# ProDoc_OASman_V4_0_2025-09-03.net
KiCad netlist of a schematic drawn in EasyEDA Pro
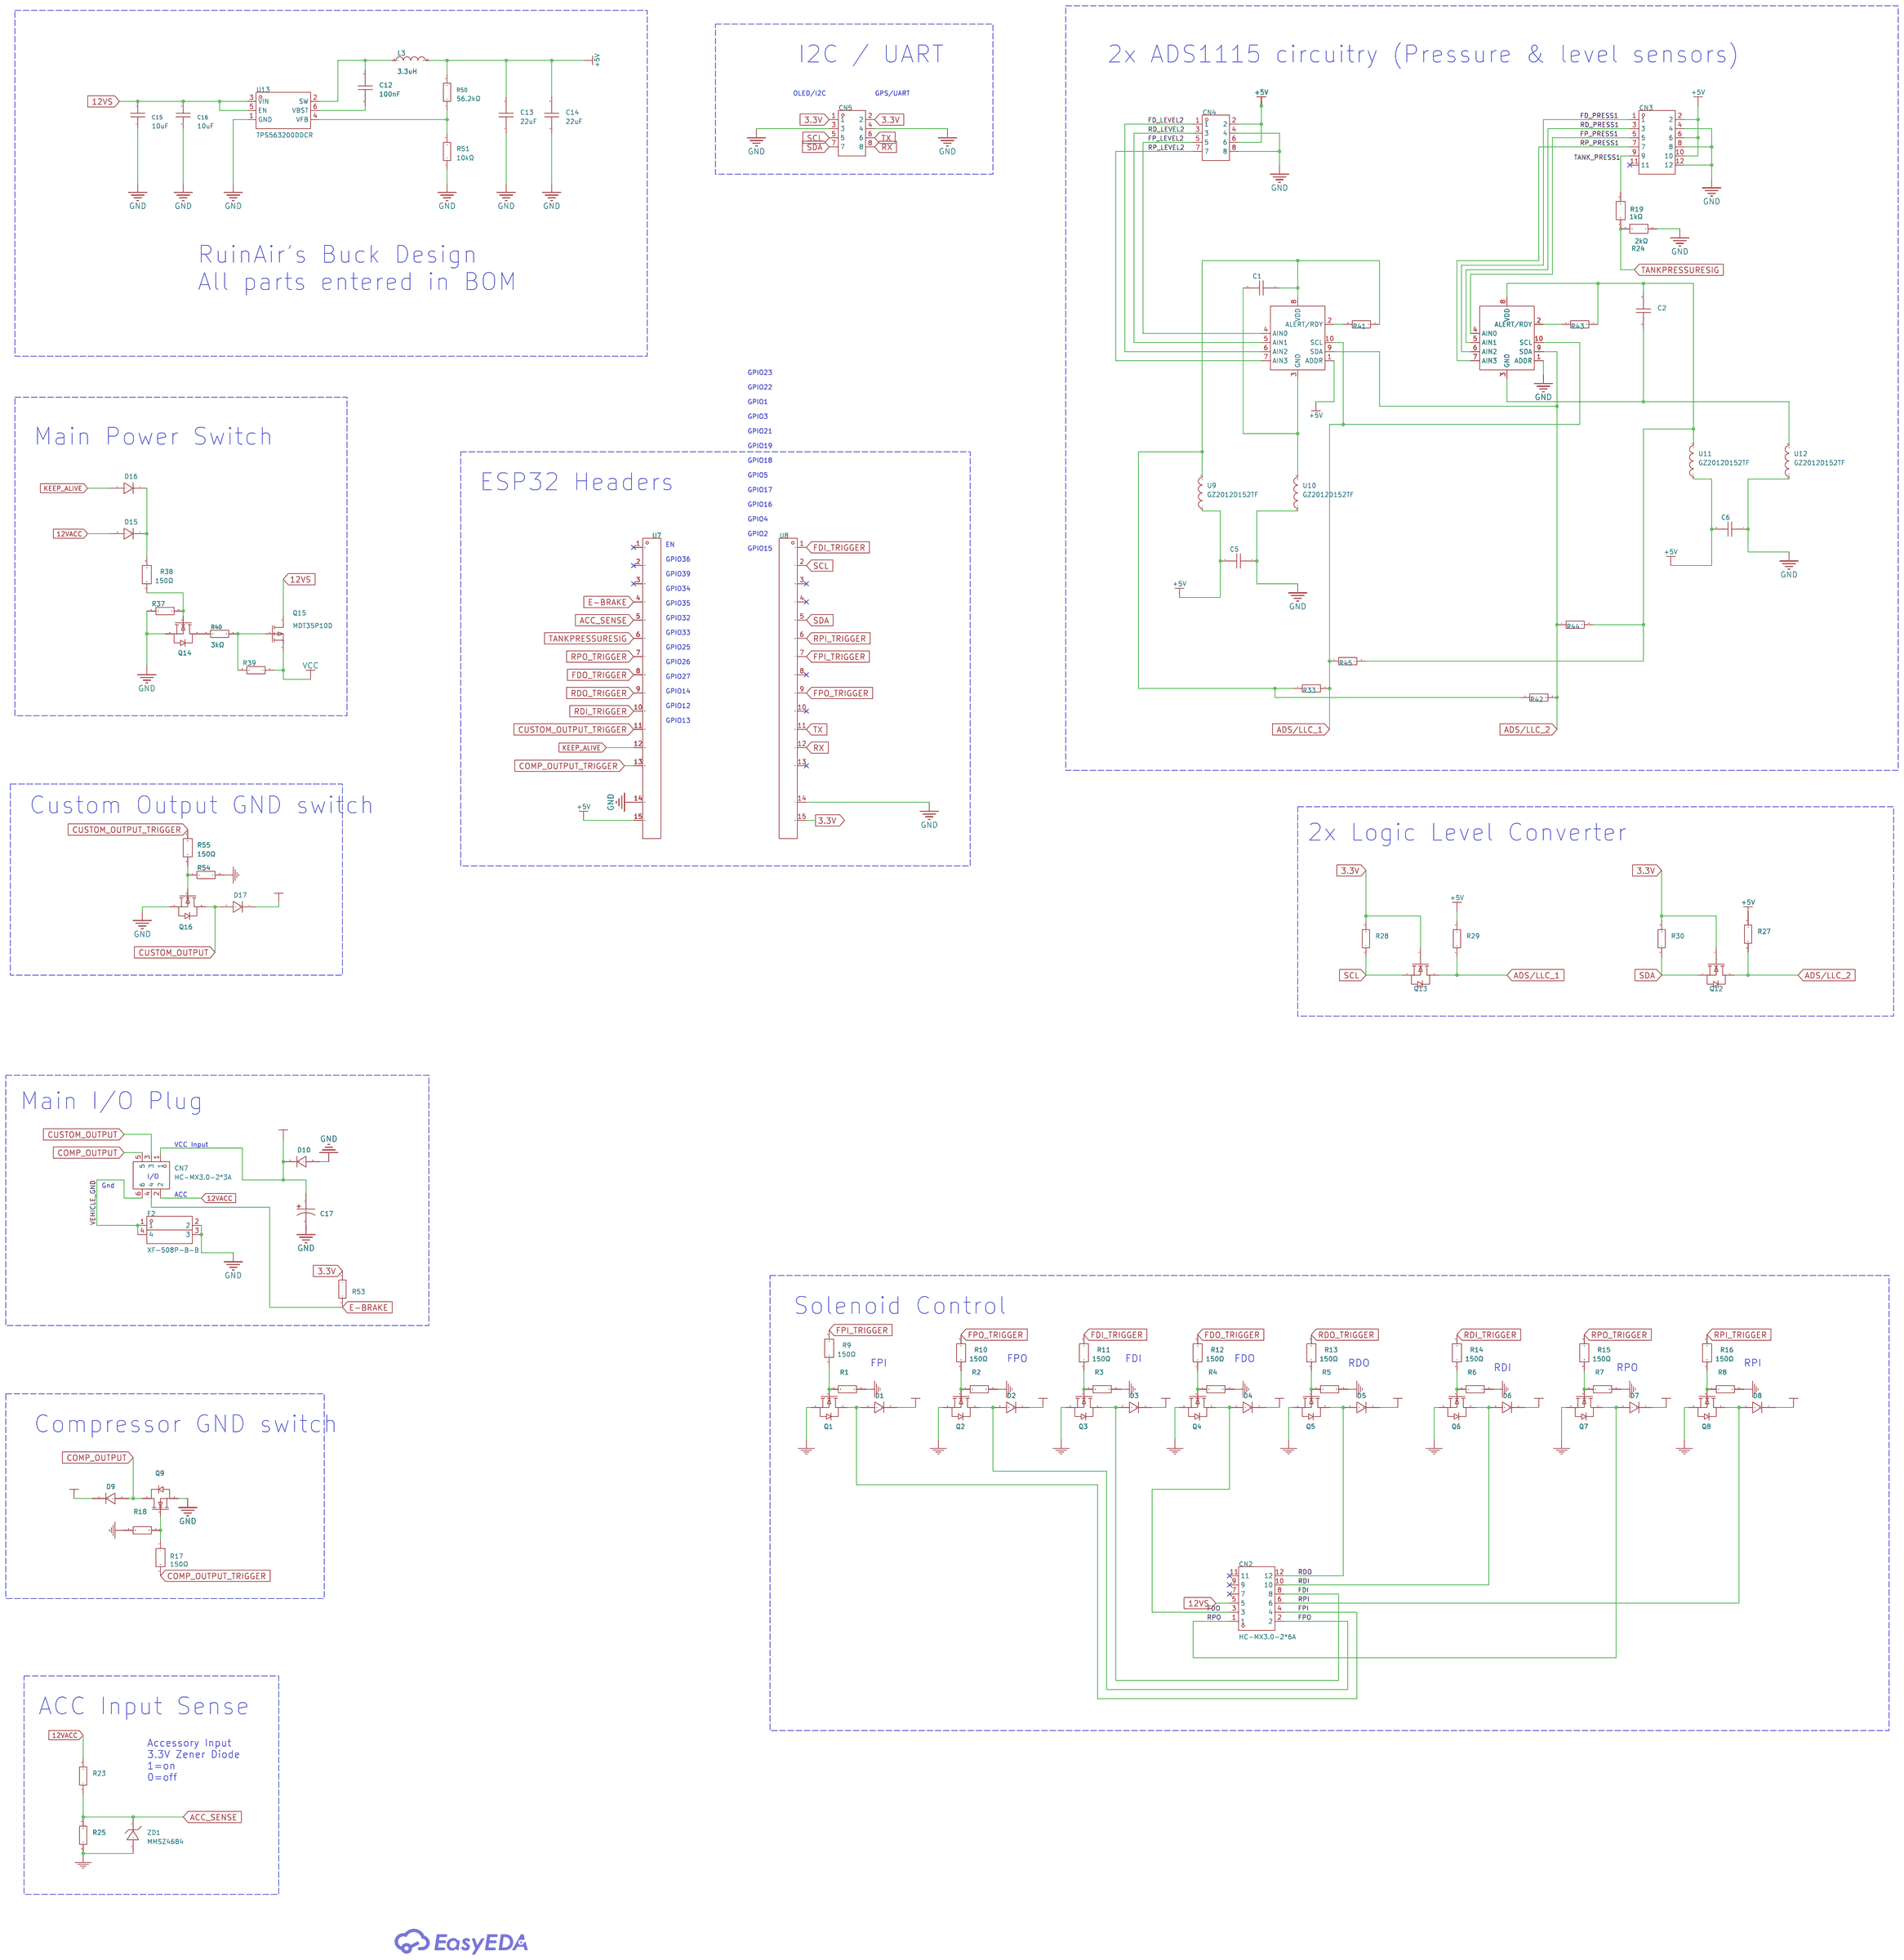
[diagram p0: schematic sheet]

(export (version "E")
  (design (tool "Eeschema 10.0.6"))
  (components
    (comp (ref "C1")
      (value "1uF")
      (footprint "easyedapro:C0603")
      (fields
        (field (name "Manufacturer Part") "GRM188R61H105KAALD")
        (field (name "Manufacturer") "muRata(村田)")
      )
      (libsource (lib "easyedapro") (part "GRM188R61H105KAALD"))
    )
    (comp (ref "C2")
      (value "1uF")
      (footprint "easyedapro:C0603")
      (fields
        (field (name "Manufacturer Part") "GRM188R61H105KAALD")
        (field (name "Manufacturer") "muRata(村田)")
      )
      (libsource (lib "easyedapro") (part "GRM188R61H105KAALD"))
    )
    (comp (ref "C5")
      (value "1uF")
      (footprint "easyedapro:C0603")
      (fields
        (field (name "Manufacturer Part") "GRM188R61H105KAALD")
        (field (name "Manufacturer") "muRata(村田)")
      )
      (libsource (lib "easyedapro") (part "GRM188R61H105KAALD"))
    )
    (comp (ref "C6")
      (value "1uF")
      (footprint "easyedapro:C0603")
      (fields
        (field (name "Manufacturer Part") "GRM188R61H105KAALD")
        (field (name "Manufacturer") "muRata(村田)")
      )
      (libsource (lib "easyedapro") (part "GRM188R61H105KAALD"))
    )
    (comp (ref "C12")
      (value "100nF")
      (footprint "easyedapro:C0402")
      (fields
        (field (name "Manufacturer Part") "CL05B104KB54PNC")
        (field (name "Manufacturer") "SAMSUNG(三星)")
      )
      (libsource (lib "easyedapro") (part "CL05B104KB54PNC"))
    )
    (comp (ref "C13")
      (value "22uF")
      (footprint "easyedapro:C0805")
      (fields
        (field (name "Manufacturer Part") "CL21A226MAQNNNE")
        (field (name "Manufacturer") "SAMSUNG(三星)")
      )
      (libsource (lib "easyedapro") (part "CL21A226MAQNNNE"))
    )
    (comp (ref "C14")
      (value "22uF")
      (footprint "easyedapro:C0805")
      (fields
        (field (name "Manufacturer Part") "CL21A226MAQNNNE")
        (field (name "Manufacturer") "SAMSUNG(三星)")
      )
      (libsource (lib "easyedapro") (part "CL21A226MAQNNNE"))
    )
    (comp (ref "C15")
      (value "10uF")
      (footprint "easyedapro:C1206")
      (fields
        (field (name "Manufacturer Part") "CL31A106KBHNNNE")
        (field (name "Manufacturer") "SAMSUNG(三星)")
      )
      (libsource (lib "easyedapro") (part "CL31A106KBHNNNE"))
    )
    (comp (ref "C16")
      (value "10uF")
      (footprint "easyedapro:C1206")
      (fields
        (field (name "Manufacturer Part") "CL31A106KBHNNNE")
        (field (name "Manufacturer") "SAMSUNG(三星)")
      )
      (libsource (lib "easyedapro") (part "CL31A106KBHNNNE"))
    )
    (comp (ref "C17")
      (value "1000uF")
      (footprint "easyedapro:CAP-SMD_BD10.0-L10.3-W10.3-FD")
      (fields (field (name "Manufacturer Part") "EEEFT1E102UP") (field (name "Manufacturer") "PANASONIC(松下)"))
      (libsource (lib "easyedapro") (part "EEEFT1E102UP"))
    )
    (comp (ref "CN2")
      (value "HC-MX3.0-2*6A")
      (footprint "easyedapro:CONN-TH_12P-P3.00_HC-MX3.0-2X6A")
      (fields (field (name "Manufacturer") "HCTL(华灿天禄)"))
      (libsource (lib "easyedapro") (part "HC-MX3.0-2*6A"))
    )
    (comp (ref "CN3")
      (value "HC-MX3.0-2*6A")
      (footprint "easyedapro:CONN-TH_12P-P3.00_HC-MX3.0-2X6A")
      (fields (field (name "Manufacturer") "HCTL(华灿天禄)"))
      (libsource (lib "easyedapro") (part "HC-MX3.0-2*6A"))
    )
    (comp (ref "CN4")
      (value "HC-MX3.0-2*4A")
      (footprint "easyedapro:CONN-TH_8P-P3.00_HC-MX3.0-2X4A")
      (fields (field (name "Manufacturer") "HCTL(华灿天禄)"))
      (libsource (lib "easyedapro") (part "HC-MX3.0-2*4A"))
    )
    (comp (ref "CN5")
      (value "HC-MX3.0-2*4A")
      (footprint "easyedapro:CONN-TH_8P-P3.00_HC-MX3.0-2X4A")
      (fields (field (name "Manufacturer") "HCTL(华灿天禄)"))
      (libsource (lib "easyedapro") (part "HC-MX3.0-2*4A"))
    )
    (comp (ref "CN7")
      (value "HC-MX3.0-2*3A")
      (footprint "easyedapro:CONN-TH_6P-P3.00_HC-MX3.0-2X3A")
      (fields (field (name "Manufacturer") "HCTL(华灿天禄)"))
      (libsource (lib "easyedapro") (part "HC-MX3.0-2*3A"))
    )
    (comp (ref "D1")
      (value "SM4007PL")
      (footprint "easyedapro:SOD-123F_L2.8-W1.8-LS3.7-RD")
      (fields (field (name "Manufacturer") "MDD(辰达半导体)"))
      (libsource (lib "easyedapro") (part "SM4007PL"))
    )
    (comp (ref "D2")
      (value "SM4007PL")
      (footprint "easyedapro:SOD-123F_L2.8-W1.8-LS3.7-RD")
      (fields (field (name "Manufacturer") "MDD(辰达半导体)"))
      (libsource (lib "easyedapro") (part "SM4007PL"))
    )
    (comp (ref "D3")
      (value "SM4007PL")
      (footprint "easyedapro:SOD-123F_L2.8-W1.8-LS3.7-RD")
      (fields (field (name "Manufacturer") "MDD(辰达半导体)"))
      (libsource (lib "easyedapro") (part "SM4007PL"))
    )
    (comp (ref "D4")
      (value "SM4007PL")
      (footprint "easyedapro:SOD-123F_L2.8-W1.8-LS3.7-RD")
      (fields (field (name "Manufacturer") "MDD(辰达半导体)"))
      (libsource (lib "easyedapro") (part "SM4007PL"))
    )
    (comp (ref "D5")
      (value "SM4007PL")
      (footprint "easyedapro:SOD-123F_L2.8-W1.8-LS3.7-RD")
      (fields (field (name "Manufacturer") "MDD(辰达半导体)"))
      (libsource (lib "easyedapro") (part "SM4007PL"))
    )
    (comp (ref "D6")
      (value "SM4007PL")
      (footprint "easyedapro:SOD-123F_L2.8-W1.8-LS3.7-RD")
      (fields (field (name "Manufacturer") "MDD(辰达半导体)"))
      (libsource (lib "easyedapro") (part "SM4007PL"))
    )
    (comp (ref "D7")
      (value "SM4007PL")
      (footprint "easyedapro:SOD-123F_L2.8-W1.8-LS3.7-RD")
      (fields (field (name "Manufacturer") "MDD(辰达半导体)"))
      (libsource (lib "easyedapro") (part "SM4007PL"))
    )
    (comp (ref "D8")
      (value "SM4007PL")
      (footprint "easyedapro:SOD-123F_L2.8-W1.8-LS3.7-RD")
      (fields (field (name "Manufacturer") "MDD(辰达半导体)"))
      (libsource (lib "easyedapro") (part "SM4007PL"))
    )
    (comp (ref "D9")
      (value "SM4007PL")
      (footprint "easyedapro:SOD-123F_L2.8-W1.8-LS3.7-RD")
      (fields (field (name "Manufacturer") "MDD(辰达半导体)"))
      (libsource (lib "easyedapro") (part "SM4007PL"))
    )
    (comp (ref "D10")
      (value "SM4007PL")
      (footprint "easyedapro:SOD-123F_L2.8-W1.8-LS3.7-RD")
      (fields (field (name "Manufacturer") "MDD(辰达半导体)"))
      (libsource (lib "easyedapro") (part "SM4007PL"))
    )
    (comp (ref "D15")
      (value "SM4007PL")
      (footprint "easyedapro:SOD-123F_L2.8-W1.8-LS3.7-RD")
      (fields (field (name "Manufacturer") "MDD(辰达半导体)"))
      (libsource (lib "easyedapro") (part "SM4007PL"))
    )
    (comp (ref "D16")
      (value "SM4007PL")
      (footprint "easyedapro:SOD-123F_L2.8-W1.8-LS3.7-RD")
      (fields (field (name "Manufacturer") "MDD(辰达半导体)"))
      (libsource (lib "easyedapro") (part "SM4007PL"))
    )
    (comp (ref "D17")
      (value "SM4007PL")
      (footprint "easyedapro:SOD-123F_L2.8-W1.8-LS3.7-RD")
      (fields (field (name "Manufacturer") "MDD(辰达半导体)"))
      (libsource (lib "easyedapro") (part "SM4007PL"))
    )
    (comp (ref "F2")
      (value "XF-508P-B-B")
      (footprint "easyedapro:FUSE-TH_4P-L16.0-W6.7")
      (fields (field (name "Manufacturer") "XFCN(兴飞)"))
      (libsource (lib "easyedapro") (part "XF-508P-B-B"))
    )
    (comp (ref "L3")
      (value "3.3uH")
      (footprint "easyedapro:IND-SMD_L4.5-W4.1_SL0420")
      (description "Inductance: Tolerance:±20% Tolerance:±20% Rated Current: Saturation Current (Isat):4A")
      (fields (field (name "Manufacturer Part") "SL0420-3R3M") (field (name "Manufacturer") "台湾陆海"))
      (libsource (lib "easyedapro") (part "SL0420-3R3M"))
    )
    (comp (ref "Q1") (value "MDT30N06L") (libsource (lib "easyedapro") (part "FQP30N06L")))
    (comp (ref "Q2") (value "MDT30N06L") (libsource (lib "easyedapro") (part "FQP30N06L")))
    (comp (ref "Q3") (value "MDT30N06L") (libsource (lib "easyedapro") (part "FQP30N06L")))
    (comp (ref "Q4") (value "MDT30N06L") (libsource (lib "easyedapro") (part "FQP30N06L")))
    (comp (ref "Q5") (value "MDT30N06L") (libsource (lib "easyedapro") (part "FQP30N06L")))
    (comp (ref "Q6") (value "MDT30N06L") (libsource (lib "easyedapro") (part "FQP30N06L")))
    (comp (ref "Q7") (value "MDT30N06L") (libsource (lib "easyedapro") (part "FQP30N06L")))
    (comp (ref "Q8") (value "MDT30N06L") (libsource (lib "easyedapro") (part "FQP30N06L")))
    (comp (ref "Q9") (value "MDT30N06L") (libsource (lib "easyedapro") (part "FQP30N06L")))
    (comp (ref "Q12")
      (value "BSS138")
      (footprint "easyedapro:SOT-23-3_L2.9-W1.6-P1.90-LS2.8-BR")
      (fields (field (name "Manufacturer") "SHIKUES(时科)"))
      (libsource (lib "easyedapro") (part "BSS138_C112239"))
    )
    (comp (ref "Q13")
      (value "BSS138")
      (footprint "easyedapro:SOT-23-3_L2.9-W1.6-P1.90-LS2.8-BR")
      (fields (field (name "Manufacturer") "SHIKUES(时科)"))
      (libsource (lib "easyedapro") (part "BSS138_C112239"))
    )
    (comp (ref "Q14") (value "MDT30N06L") (libsource (lib "easyedapro") (part "FQP30N06L")))
    (comp (ref "Q15")
      (value "MDT35P10D")
      (footprint "easyedapro:TO-252-2_L6.6-W6.1-P4.57-LS9.9-BR-CW")
      (fields (field (name "Manufacturer") "minos(迈诺斯)"))
      (libsource (lib "easyedapro") (part "MDT35P10D"))
    )
    (comp (ref "Q16") (value "MDT30N06L") (libsource (lib "easyedapro") (part "FQP30N06L")))
    (comp (ref "R1")
      (value "10kΩ")
      (footprint "easyedapro:R1206")
      (fields
        (field (name "Manufacturer Part") "1206W4F1002T5E")
        (field (name "Manufacturer") "UNI-ROYAL(厚声)")
      )
      (libsource (lib "easyedapro") (part "1206W4F1002T5E"))
    )
    (comp (ref "R2")
      (value "10kΩ")
      (footprint "easyedapro:R1206")
      (fields
        (field (name "Manufacturer Part") "1206W4F1002T5E")
        (field (name "Manufacturer") "UNI-ROYAL(厚声)")
      )
      (libsource (lib "easyedapro") (part "1206W4F1002T5E"))
    )
    (comp (ref "R3")
      (value "10kΩ")
      (footprint "easyedapro:R1206")
      (fields
        (field (name "Manufacturer Part") "1206W4F1002T5E")
        (field (name "Manufacturer") "UNI-ROYAL(厚声)")
      )
      (libsource (lib "easyedapro") (part "1206W4F1002T5E"))
    )
    (comp (ref "R4")
      (value "10kΩ")
      (footprint "easyedapro:R1206")
      (fields
        (field (name "Manufacturer Part") "1206W4F1002T5E")
        (field (name "Manufacturer") "UNI-ROYAL(厚声)")
      )
      (libsource (lib "easyedapro") (part "1206W4F1002T5E"))
    )
    (comp (ref "R5")
      (value "10kΩ")
      (footprint "easyedapro:R1206")
      (fields
        (field (name "Manufacturer Part") "1206W4F1002T5E")
        (field (name "Manufacturer") "UNI-ROYAL(厚声)")
      )
      (libsource (lib "easyedapro") (part "1206W4F1002T5E"))
    )
    (comp (ref "R6")
      (value "10kΩ")
      (footprint "easyedapro:R1206")
      (fields
        (field (name "Manufacturer Part") "1206W4F1002T5E")
        (field (name "Manufacturer") "UNI-ROYAL(厚声)")
      )
      (libsource (lib "easyedapro") (part "1206W4F1002T5E"))
    )
    (comp (ref "R7")
      (value "10kΩ")
      (footprint "easyedapro:R1206")
      (fields
        (field (name "Manufacturer Part") "1206W4F1002T5E")
        (field (name "Manufacturer") "UNI-ROYAL(厚声)")
      )
      (libsource (lib "easyedapro") (part "1206W4F1002T5E"))
    )
    (comp (ref "R8")
      (value "10kΩ")
      (footprint "easyedapro:R1206")
      (fields
        (field (name "Manufacturer Part") "1206W4F1002T5E")
        (field (name "Manufacturer") "UNI-ROYAL(厚声)")
      )
      (libsource (lib "easyedapro") (part "1206W4F1002T5E"))
    )
    (comp (ref "R9")
      (value "150Ω")
      (footprint "easyedapro:R1206")
      (fields (field (name "Manufacturer Part") "FRC1206J151 TS") (field (name "Manufacturer") "FOJAN(富捷)"))
      (libsource (lib "easyedapro") (part "FRC1206J151 TS"))
    )
    (comp (ref "R10")
      (value "150Ω")
      (footprint "easyedapro:R1206")
      (fields (field (name "Manufacturer Part") "FRC1206J151 TS") (field (name "Manufacturer") "FOJAN(富捷)"))
      (libsource (lib "easyedapro") (part "FRC1206J151 TS"))
    )
    (comp (ref "R11")
      (value "150Ω")
      (footprint "easyedapro:R1206")
      (fields (field (name "Manufacturer Part") "FRC1206J151 TS") (field (name "Manufacturer") "FOJAN(富捷)"))
      (libsource (lib "easyedapro") (part "FRC1206J151 TS"))
    )
    (comp (ref "R12")
      (value "150Ω")
      (footprint "easyedapro:R1206")
      (fields (field (name "Manufacturer Part") "FRC1206J151 TS") (field (name "Manufacturer") "FOJAN(富捷)"))
      (libsource (lib "easyedapro") (part "FRC1206J151 TS"))
    )
    (comp (ref "R13")
      (value "150Ω")
      (footprint "easyedapro:R1206")
      (fields (field (name "Manufacturer Part") "FRC1206J151 TS") (field (name "Manufacturer") "FOJAN(富捷)"))
      (libsource (lib "easyedapro") (part "FRC1206J151 TS"))
    )
    (comp (ref "R14")
      (value "150Ω")
      (footprint "easyedapro:R1206")
      (fields (field (name "Manufacturer Part") "FRC1206J151 TS") (field (name "Manufacturer") "FOJAN(富捷)"))
      (libsource (lib "easyedapro") (part "FRC1206J151 TS"))
    )
    (comp (ref "R15")
      (value "150Ω")
      (footprint "easyedapro:R1206")
      (fields (field (name "Manufacturer Part") "FRC1206J151 TS") (field (name "Manufacturer") "FOJAN(富捷)"))
      (libsource (lib "easyedapro") (part "FRC1206J151 TS"))
    )
    (comp (ref "R16")
      (value "150Ω")
      (footprint "easyedapro:R1206")
      (fields (field (name "Manufacturer Part") "FRC1206J151 TS") (field (name "Manufacturer") "FOJAN(富捷)"))
      (libsource (lib "easyedapro") (part "FRC1206J151 TS"))
    )
    (comp (ref "R17")
      (value "150Ω")
      (footprint "easyedapro:R1206")
      (fields (field (name "Manufacturer Part") "FRC1206J151 TS") (field (name "Manufacturer") "FOJAN(富捷)"))
      (libsource (lib "easyedapro") (part "FRC1206J151 TS"))
    )
    (comp (ref "R18")
      (value "10kΩ")
      (footprint "easyedapro:R1206")
      (fields
        (field (name "Manufacturer Part") "1206W4F1002T5E")
        (field (name "Manufacturer") "UNI-ROYAL(厚声)")
      )
      (libsource (lib "easyedapro") (part "1206W4F1002T5E"))
    )
    (comp (ref "R19")
      (value "1kΩ")
      (footprint "easyedapro:R1206")
      (fields (field (name "Manufacturer Part") "FRC1206J102 TS") (field (name "Manufacturer") "FOJAN(富捷)"))
      (libsource (lib "easyedapro") (part "FRC1206J102 TS"))
    )
    (comp (ref "R23")
      (value "10kΩ")
      (footprint "easyedapro:R1206")
      (fields
        (field (name "Manufacturer Part") "1206W4F1002T5E")
        (field (name "Manufacturer") "UNI-ROYAL(厚声)")
      )
      (libsource (lib "easyedapro") (part "1206W4F1002T5E"))
    )
    (comp (ref "R24")
      (value "2kΩ")
      (footprint "easyedapro:R1206")
      (fields (field (name "Manufacturer Part") "FRC1206J202 TS") (field (name "Manufacturer") "FOJAN(富捷)"))
      (libsource (lib "easyedapro") (part "FRC1206J202 TS"))
    )
    (comp (ref "R25")
      (value "10kΩ")
      (footprint "easyedapro:R1206")
      (fields
        (field (name "Manufacturer Part") "1206W4F1002T5E")
        (field (name "Manufacturer") "UNI-ROYAL(厚声)")
      )
      (libsource (lib "easyedapro") (part "1206W4F1002T5E"))
    )
    (comp (ref "R27")
      (value "10kΩ")
      (footprint "easyedapro:R1206")
      (fields
        (field (name "Manufacturer Part") "1206W4F1002T5E")
        (field (name "Manufacturer") "UNI-ROYAL(厚声)")
      )
      (libsource (lib "easyedapro") (part "1206W4F1002T5E"))
    )
    (comp (ref "R28")
      (value "10kΩ")
      (footprint "easyedapro:R1206")
      (fields
        (field (name "Manufacturer Part") "1206W4F1002T5E")
        (field (name "Manufacturer") "UNI-ROYAL(厚声)")
      )
      (libsource (lib "easyedapro") (part "1206W4F1002T5E"))
    )
    (comp (ref "R29")
      (value "10kΩ")
      (footprint "easyedapro:R1206")
      (fields
        (field (name "Manufacturer Part") "1206W4F1002T5E")
        (field (name "Manufacturer") "UNI-ROYAL(厚声)")
      )
      (libsource (lib "easyedapro") (part "1206W4F1002T5E"))
    )
    (comp (ref "R30")
      (value "10kΩ")
      (footprint "easyedapro:R1206")
      (fields
        (field (name "Manufacturer Part") "1206W4F1002T5E")
        (field (name "Manufacturer") "UNI-ROYAL(厚声)")
      )
      (libsource (lib "easyedapro") (part "1206W4F1002T5E"))
    )
    (comp (ref "R33")
      (value "1MΩ")
      (footprint "easyedapro:R1206")
      (fields
        (field (name "Manufacturer Part") "1206W4F1004T5E")
        (field (name "Manufacturer") "UNI-ROYAL(厚声)")
      )
      (libsource (lib "easyedapro") (part "1206W4F1004T5E"))
    )
    (comp (ref "R37")
      (value "10kΩ")
      (footprint "easyedapro:R1206")
      (fields
        (field (name "Manufacturer Part") "1206W4F1002T5E")
        (field (name "Manufacturer") "UNI-ROYAL(厚声)")
      )
      (libsource (lib "easyedapro") (part "1206W4F1002T5E"))
    )
    (comp (ref "R38")
      (value "150Ω")
      (footprint "easyedapro:R1206")
      (fields (field (name "Manufacturer Part") "FRC1206J151 TS") (field (name "Manufacturer") "FOJAN(富捷)"))
      (libsource (lib "easyedapro") (part "FRC1206J151 TS"))
    )
    (comp (ref "R39")
      (value "10kΩ")
      (footprint "easyedapro:R1206")
      (fields
        (field (name "Manufacturer Part") "1206W4F1002T5E")
        (field (name "Manufacturer") "UNI-ROYAL(厚声)")
      )
      (libsource (lib "easyedapro") (part "1206W4F1002T5E"))
    )
    (comp (ref "R40")
      (value "3kΩ")
      (footprint "easyedapro:R1206")
      (fields
        (field (name "Manufacturer Part") "1206W4F3001T5E")
        (field (name "Manufacturer") "UNI-ROYAL(厚声)")
      )
      (libsource (lib "easyedapro") (part "1206W4F3001T5E"))
    )
    (comp (ref "R41")
      (value "1MΩ")
      (footprint "easyedapro:R1206")
      (fields
        (field (name "Manufacturer Part") "1206W4F1004T5E")
        (field (name "Manufacturer") "UNI-ROYAL(厚声)")
      )
      (libsource (lib "easyedapro") (part "1206W4F1004T5E"))
    )
    (comp (ref "R42")
      (value "1MΩ")
      (footprint "easyedapro:R1206")
      (fields
        (field (name "Manufacturer Part") "1206W4F1004T5E")
        (field (name "Manufacturer") "UNI-ROYAL(厚声)")
      )
      (libsource (lib "easyedapro") (part "1206W4F1004T5E"))
    )
    (comp (ref "R43")
      (value "1MΩ")
      (footprint "easyedapro:R1206")
      (fields
        (field (name "Manufacturer Part") "1206W4F1004T5E")
        (field (name "Manufacturer") "UNI-ROYAL(厚声)")
      )
      (libsource (lib "easyedapro") (part "1206W4F1004T5E"))
    )
    (comp (ref "R44")
      (value "1MΩ")
      (footprint "easyedapro:R1206")
      (fields
        (field (name "Manufacturer Part") "1206W4F1004T5E")
        (field (name "Manufacturer") "UNI-ROYAL(厚声)")
      )
      (libsource (lib "easyedapro") (part "1206W4F1004T5E"))
    )
    (comp (ref "R45")
      (value "1MΩ")
      (footprint "easyedapro:R1206")
      (fields
        (field (name "Manufacturer Part") "1206W4F1004T5E")
        (field (name "Manufacturer") "UNI-ROYAL(厚声)")
      )
      (libsource (lib "easyedapro") (part "1206W4F1004T5E"))
    )
    (comp (ref "R50")
      (value "56.2kΩ")
      (footprint "easyedapro:R0402")
      (fields
        (field (name "Manufacturer Part") "0402WGF5622TCE")
        (field (name "Manufacturer") "UNI-ROYAL(厚声)")
      )
      (libsource (lib "easyedapro") (part "0402WGF5622TCE"))
    )
    (comp (ref "R51")
      (value "10kΩ")
      (footprint "easyedapro:R0402")
      (fields
        (field (name "Manufacturer Part") "0402WGF1002TCE")
        (field (name "Manufacturer") "UNI-ROYAL(厚声)")
      )
      (libsource (lib "easyedapro") (part "0402WGF1002TCE"))
    )
    (comp (ref "R53")
      (value "10kΩ")
      (footprint "easyedapro:R1206")
      (fields
        (field (name "Manufacturer Part") "1206W4F1002T5E")
        (field (name "Manufacturer") "UNI-ROYAL(厚声)")
      )
      (libsource (lib "easyedapro") (part "1206W4F1002T5E"))
    )
    (comp (ref "R54")
      (value "10kΩ")
      (footprint "easyedapro:R1206")
      (fields
        (field (name "Manufacturer Part") "1206W4F1002T5E")
        (field (name "Manufacturer") "UNI-ROYAL(厚声)")
      )
      (libsource (lib "easyedapro") (part "1206W4F1002T5E"))
    )
    (comp (ref "R55")
      (value "150Ω")
      (footprint "easyedapro:R1206")
      (fields (field (name "Manufacturer Part") "FRC1206J151 TS") (field (name "Manufacturer") "FOJAN(富捷)"))
      (libsource (lib "easyedapro") (part "FRC1206J151 TS"))
    )
    (comp (ref "U4")
      (value "ADS1115IDGSR")
      (fields (field (name "Manufacturer") "TI(德州仪器)"))
      (libsource (lib "easyedapro") (part "Analog_ADC_ADS1115IDGS"))
    )
    (comp (ref "U5")
      (value "ADS1115IDGSR")
      (fields (field (name "Manufacturer") "TI(德州仪器)"))
      (libsource (lib "easyedapro") (part "Analog_ADC_ADS1115IDGS"))
    )
    (comp (ref "U7")
      (value "PM2.54-1*15")
      (footprint "easyedapro:HDR-TH_15P-P2.54-V-F")
      (description "Holes Structure:1x15P Pitch:2.54mm Number of Rows:Plugin Contact Plating:Gold")
      (fields (field (name "Manufacturer") "ZHOURI(洲日)"))
      (libsource (lib "easyedapro") (part "FH2.54-09-15PZD"))
    )
    (comp (ref "U8")
      (value "PM2.54-1*15")
      (footprint "easyedapro:HDR-TH_15P-P2.54-V-F")
      (description "Holes Structure:1x15P Pitch:2.54mm Number of Rows:Plugin Contact Plating:Gold")
      (fields (field (name "Manufacturer") "ZHOURI(洲日)"))
      (libsource (lib "easyedapro") (part "FH2.54-09-15PZD"))
    )
    (comp (ref "U9")
      (value "GZ2012D152TF")
      (fields (field (name "Manufacturer") "Sunlord(顺络)"))
      (libsource (lib "easyedapro") (part "MMZ2012Y152BT000"))
    )
    (comp (ref "U10")
      (value "GZ2012D152TF")
      (fields (field (name "Manufacturer") "Sunlord(顺络)"))
      (libsource (lib "easyedapro") (part "MMZ2012Y152BT000"))
    )
    (comp (ref "U11")
      (value "GZ2012D152TF")
      (fields (field (name "Manufacturer") "Sunlord(顺络)"))
      (libsource (lib "easyedapro") (part "MMZ2012Y152BT000"))
    )
    (comp (ref "U12")
      (value "GZ2012D152TF")
      (fields (field (name "Manufacturer") "Sunlord(顺络)"))
      (libsource (lib "easyedapro") (part "MMZ2012Y152BT000"))
    )
    (comp (ref "U13")
      (value "TPS563200DDCR")
      (footprint "easyedapro:SOT-23-6_L2.9-W1.6-P0.95-LS2.8-BR")
      (fields (field (name "Manufacturer") "TI(德州仪器)"))
      (libsource (lib "easyedapro") (part "TPS563200DDCR"))
    )
    (comp (ref "ZD1")
      (value "MMSZ4684")
      (footprint "easyedapro:SOD-123_L2.8-W1.8-LS3.7-RD")
      (fields (field (name "Manufacturer") "CJ(江苏长电/长晶)"))
      (libsource (lib "easyedapro") (part "MMSZ4684"))
    )
  )
  (nets
    (net (code "1") (name "+5V") (class "Default")
      (node (ref "C13") (pin "2") (pinfunction "2_2") (pintype "unspecified"))
      (node (ref "C14") (pin "2") (pinfunction "2_2") (pintype "unspecified"))
      (node (ref "C5") (pin "2") (pinfunction "2_2") (pintype "unspecified"))
      (node (ref "C6") (pin "2") (pinfunction "2_2") (pintype "unspecified"))
      (node (ref "CN3") (pin "10") (pinfunction "10_10") (pintype "unspecified"))
      (node (ref "CN3") (pin "2") (pinfunction "2_2") (pintype "unspecified"))
      (node (ref "CN3") (pin "6") (pinfunction "6_6") (pintype "unspecified"))
      (node (ref "CN4") (pin "2") (pinfunction "2_2") (pintype "unspecified"))
      (node (ref "CN4") (pin "6") (pinfunction "6_6") (pintype "unspecified"))
      (node (ref "L3") (pin "2") (pinfunction "2_2") (pintype "unspecified"))
      (node (ref "R27") (pin "1") (pinfunction "1_1") (pintype "input"))
      (node (ref "R29") (pin "2") (pinfunction "2_2") (pintype "input"))
      (node (ref "R50") (pin "2") (pinfunction "2_2") (pintype "input"))
      (node (ref "U11") (pin "1") (pinfunction "1_1") (pintype "input"))
      (node (ref "U4") (pin "1") (pinfunction "ADDR_1") (pintype "input"))
      (node (ref "U7") (pin "15") (pinfunction "15_15") (pintype "unspecified"))
      (node (ref "U9") (pin "1") (pinfunction "1_1") (pintype "input"))
    )
    (net (code "2") (name "/FDI") (class "Default")
      (node (ref "CN2") (pin "8") (pinfunction "8_8") (pintype "unspecified"))
      (node (ref "D3") (pin "2") (pinfunction "A_2") (pintype "unspecified"))
      (node (ref "Q3") (pin "2") (pinfunction "D_2") (pintype "unspecified"))
    )
    (net (code "3") (name "/FDO") (class "Default")
      (node (ref "CN2") (pin "3") (pinfunction "3_3") (pintype "unspecified"))
      (node (ref "D4") (pin "2") (pinfunction "A_2") (pintype "unspecified"))
      (node (ref "Q4") (pin "2") (pinfunction "D_2") (pintype "unspecified"))
    )
    (net (code "4") (name "/FD_LEVEL2") (class "Default")
      (node (ref "CN4") (pin "1") (pinfunction "1_1") (pintype "unspecified"))
      (node (ref "U4") (pin "6") (pinfunction "AIN2_6") (pintype "input"))
    )
    (net (code "5") (name "/FD_PRESS1") (class "Default")
      (node (ref "CN3") (pin "1") (pinfunction "1_1") (pintype "unspecified"))
      (node (ref "U5") (pin "6") (pinfunction "AIN2_6") (pintype "input"))
    )
    (net (code "6") (name "/FPI") (class "Default")
      (node (ref "CN2") (pin "4") (pinfunction "4_4") (pintype "unspecified"))
      (node (ref "D1") (pin "2") (pinfunction "A_2") (pintype "unspecified"))
      (node (ref "Q1") (pin "2") (pinfunction "D_2") (pintype "unspecified"))
    )
    (net (code "7") (name "/FPO") (class "Default")
      (node (ref "CN2") (pin "2") (pinfunction "2_2") (pintype "unspecified"))
      (node (ref "D2") (pin "2") (pinfunction "A_2") (pintype "unspecified"))
      (node (ref "Q2") (pin "2") (pinfunction "D_2") (pintype "unspecified"))
    )
    (net (code "8") (name "/FP_LEVEL2") (class "Default")
      (node (ref "CN4") (pin "5") (pinfunction "5_5") (pintype "unspecified"))
      (node (ref "U4") (pin "4") (pinfunction "AIN0_4") (pintype "input"))
    )
    (net (code "9") (name "/FP_PRESS1") (class "Default")
      (node (ref "CN3") (pin "5") (pinfunction "5_5") (pintype "unspecified"))
      (node (ref "U5") (pin "4") (pinfunction "AIN0_4") (pintype "input"))
    )
    (net (code "10") (name "/RDI") (class "Default")
      (node (ref "CN2") (pin "10") (pinfunction "10_10") (pintype "unspecified"))
      (node (ref "D6") (pin "2") (pinfunction "A_2") (pintype "unspecified"))
      (node (ref "Q6") (pin "2") (pinfunction "D_2") (pintype "unspecified"))
    )
    (net (code "11") (name "/RDO") (class "Default")
      (node (ref "CN2") (pin "12") (pinfunction "12_12") (pintype "unspecified"))
      (node (ref "D5") (pin "2") (pinfunction "A_2") (pintype "unspecified"))
      (node (ref "Q5") (pin "2") (pinfunction "D_2") (pintype "unspecified"))
    )
    (net (code "12") (name "/RD_LEVEL2") (class "Default")
      (node (ref "CN4") (pin "3") (pinfunction "3_3") (pintype "unspecified"))
      (node (ref "U4") (pin "5") (pinfunction "AIN1_5") (pintype "input"))
    )
    (net (code "13") (name "/RD_PRESS1") (class "Default")
      (node (ref "CN3") (pin "3") (pinfunction "3_3") (pintype "unspecified"))
      (node (ref "U5") (pin "5") (pinfunction "AIN1_5") (pintype "input"))
    )
    (net (code "14") (name "/RPI") (class "Default")
      (node (ref "CN2") (pin "6") (pinfunction "6_6") (pintype "unspecified"))
      (node (ref "D8") (pin "2") (pinfunction "A_2") (pintype "unspecified"))
      (node (ref "Q8") (pin "2") (pinfunction "D_2") (pintype "unspecified"))
    )
    (net (code "15") (name "/RPO") (class "Default")
      (node (ref "CN2") (pin "1") (pinfunction "1_1") (pintype "unspecified"))
      (node (ref "D7") (pin "2") (pinfunction "A_2") (pintype "unspecified"))
      (node (ref "Q7") (pin "2") (pinfunction "D_2") (pintype "unspecified"))
    )
    (net (code "16") (name "/RP_LEVEL2") (class "Default")
      (node (ref "CN4") (pin "7") (pinfunction "7_7") (pintype "unspecified"))
      (node (ref "U4") (pin "7") (pinfunction "AIN3_7") (pintype "input"))
    )
    (net (code "17") (name "/RP_PRESS1") (class "Default")
      (node (ref "CN3") (pin "7") (pinfunction "7_7") (pintype "unspecified"))
      (node (ref "U5") (pin "7") (pinfunction "AIN3_7") (pintype "input"))
    )
    (net (code "18") (name "/TANK_PRESS1") (class "Default")
      (node (ref "CN3") (pin "9") (pinfunction "9_9") (pintype "unspecified"))
      (node (ref "R19") (pin "2") (pinfunction "2_2") (pintype "unspecified"))
    )
    (net (code "19") (name "/VEHICLE_GND") (class "Default")
      (node (ref "CN7") (pin "6") (pinfunction "6_6") (pintype "unspecified"))
      (node (ref "F2") (pin "1") (pinfunction "1_1") (pintype "unspecified"))
      (node (ref "F2") (pin "4") (pinfunction "4_4") (pintype "unspecified"))
    )
    (net (code "20") (name "3.3V") (class "Default")
      (node (ref "CN5") (pin "1") (pinfunction "1_1") (pintype "unspecified"))
      (node (ref "CN5") (pin "2") (pinfunction "2_2") (pintype "unspecified"))
      (node (ref "Q12") (pin "1") (pinfunction "G_1") (pintype "unspecified"))
      (node (ref "Q13") (pin "1") (pinfunction "G_1") (pintype "unspecified"))
      (node (ref "R28") (pin "2") (pinfunction "2_2") (pintype "input"))
      (node (ref "R30") (pin "2") (pinfunction "2_2") (pintype "input"))
      (node (ref "R53") (pin "1") (pinfunction "1_1") (pintype "input"))
      (node (ref "U8") (pin "15") (pinfunction "15_15") (pintype "unspecified"))
    )
    (net (code "21") (name "12VACC") (class "Default")
      (node (ref "CN7") (pin "2") (pinfunction "2_2") (pintype "unspecified"))
      (node (ref "D15") (pin "2") (pinfunction "A_2") (pintype "unspecified"))
      (node (ref "R23") (pin "2") (pinfunction "2_2") (pintype "input"))
    )
    (net (code "22") (name "12VS") (class "Default")
      (node (ref "C15") (pin "2") (pinfunction "2_2") (pintype "input"))
      (node (ref "C16") (pin "2") (pinfunction "2_2") (pintype "input"))
      (node (ref "CN2") (pin "5") (pinfunction "5_5") (pintype "unspecified"))
      (node (ref "Q15") (pin "2") (pinfunction "D_2") (pintype "unspecified"))
      (node (ref "U13") (pin "3") (pinfunction "VIN_3") (pintype "unspecified"))
      (node (ref "U13") (pin "5") (pinfunction "EN_5") (pintype "unspecified"))
    )
    (net (code "23") (name "ACC_SENSE") (class "Default")
      (node (ref "R23") (pin "1") (pinfunction "1_1") (pintype "input"))
      (node (ref "R25") (pin "2") (pinfunction "2_2") (pintype "input"))
      (node (ref "U7") (pin "5") (pinfunction "5_5") (pintype "unspecified"))
      (node (ref "ZD1") (pin "1") (pinfunction "K_1") (pintype "unspecified"))
    )
    (net (code "24") (name "ADS{slash}LLC_1") (class "Default")
      (node (ref "Q13") (pin "3") (pinfunction "D_3") (pintype "unspecified"))
      (node (ref "R29") (pin "1") (pinfunction "1_1") (pintype "input"))
      (node (ref "R33") (pin "2") (pinfunction "2_2") (pintype "input"))
      (node (ref "R45") (pin "1") (pinfunction "1_1") (pintype "input"))
      (node (ref "U4") (pin "10") (pinfunction "SCL_10") (pintype "input"))
      (node (ref "U5") (pin "10") (pinfunction "SCL_10") (pintype "input"))
    )
    (net (code "25") (name "ADS{slash}LLC_2") (class "Default")
      (node (ref "Q12") (pin "3") (pinfunction "D_3") (pintype "unspecified"))
      (node (ref "R27") (pin "2") (pinfunction "2_2") (pintype "input"))
      (node (ref "R42") (pin "2") (pinfunction "2_2") (pintype "input"))
      (node (ref "R44") (pin "1") (pinfunction "1_1") (pintype "input"))
      (node (ref "U4") (pin "9") (pinfunction "SDA_9") (pintype "bidirectional"))
      (node (ref "U5") (pin "9") (pinfunction "SDA_9") (pintype "bidirectional"))
    )
    (net (code "26") (name "COMP_OUTPUT") (class "Default")
      (node (ref "CN7") (pin "5") (pinfunction "5_5") (pintype "unspecified"))
      (node (ref "D9") (pin "2") (pinfunction "A_2") (pintype "unspecified"))
      (node (ref "Q9") (pin "2") (pinfunction "D_2") (pintype "unspecified"))
    )
    (net (code "27") (name "COMP_OUTPUT_TRIGGER") (class "Default")
      (node (ref "R17") (pin "2") (pinfunction "2_2") (pintype "unspecified"))
      (node (ref "U7") (pin "13") (pinfunction "13_13") (pintype "unspecified"))
    )
    (net (code "28") (name "CUSTOM_OUTPUT") (class "Default")
      (node (ref "CN7") (pin "3") (pinfunction "3_3") (pintype "unspecified"))
      (node (ref "D17") (pin "2") (pinfunction "A_2") (pintype "unspecified"))
      (node (ref "Q16") (pin "2") (pinfunction "D_2") (pintype "unspecified"))
    )
    (net (code "29") (name "CUSTOM_OUTPUT_TRIGGER") (class "Default")
      (node (ref "R55") (pin "2") (pinfunction "2_2") (pintype "unspecified"))
      (node (ref "U7") (pin "11") (pinfunction "11_11") (pintype "unspecified"))
    )
    (net (code "30") (name "E-BRAKE") (class "Default")
      (node (ref "CN7") (pin "4") (pinfunction "4_4") (pintype "unspecified"))
      (node (ref "R53") (pin "2") (pinfunction "2_2") (pintype "input"))
      (node (ref "U7") (pin "4") (pinfunction "4_4") (pintype "unspecified"))
    )
    (net (code "31") (name "FDI_TRIGGER") (class "Default")
      (node (ref "R11") (pin "2") (pinfunction "2_2") (pintype "unspecified"))
      (node (ref "U8") (pin "1") (pinfunction "1_1") (pintype "unspecified"))
    )
    (net (code "32") (name "FDO_TRIGGER") (class "Default")
      (node (ref "R12") (pin "2") (pinfunction "2_2") (pintype "unspecified"))
      (node (ref "U7") (pin "8") (pinfunction "8_8") (pintype "unspecified"))
    )
    (net (code "33") (name "FPI_TRIGGER") (class "Default")
      (node (ref "R9") (pin "2") (pinfunction "2_2") (pintype "unspecified"))
      (node (ref "U8") (pin "7") (pinfunction "7_7") (pintype "unspecified"))
    )
    (net (code "34") (name "FPO_TRIGGER") (class "Default")
      (node (ref "R10") (pin "2") (pinfunction "2_2") (pintype "unspecified"))
      (node (ref "U8") (pin "9") (pinfunction "9_9") (pintype "unspecified"))
    )
    (net (code "35") (name "GND") (class "Default")
      (node (ref "C13") (pin "1") (pinfunction "1_1") (pintype "unspecified"))
      (node (ref "C14") (pin "1") (pinfunction "1_1") (pintype "unspecified"))
      (node (ref "C15") (pin "1") (pinfunction "1_1") (pintype "input"))
      (node (ref "C16") (pin "1") (pinfunction "1_1") (pintype "input"))
      (node (ref "C17") (pin "2") (pinfunction "2_2") (pintype "input"))
      (node (ref "C5") (pin "1") (pinfunction "1_1") (pintype "unspecified"))
      (node (ref "C6") (pin "1") (pinfunction "1_1") (pintype "unspecified"))
      (node (ref "CN3") (pin "12") (pinfunction "12_12") (pintype "unspecified"))
      (node (ref "CN3") (pin "4") (pinfunction "4_4") (pintype "unspecified"))
      (node (ref "CN3") (pin "8") (pinfunction "8_8") (pintype "unspecified"))
      (node (ref "CN4") (pin "4") (pinfunction "4_4") (pintype "unspecified"))
      (node (ref "CN4") (pin "8") (pinfunction "8_8") (pintype "unspecified"))
      (node (ref "CN5") (pin "3") (pinfunction "3_3") (pintype "unspecified"))
      (node (ref "CN5") (pin "4") (pinfunction "4_4") (pintype "unspecified"))
      (node (ref "D10") (pin "2") (pinfunction "A_2") (pintype "unspecified"))
      (node (ref "F2") (pin "2") (pinfunction "2_2") (pintype "unspecified"))
      (node (ref "F2") (pin "3") (pinfunction "3_3") (pintype "unspecified"))
      (node (ref "Q1") (pin "3") (pinfunction "S_3") (pintype "unspecified"))
      (node (ref "Q14") (pin "3") (pinfunction "S_3") (pintype "unspecified"))
      (node (ref "Q16") (pin "3") (pinfunction "S_3") (pintype "unspecified"))
      (node (ref "Q2") (pin "3") (pinfunction "S_3") (pintype "unspecified"))
      (node (ref "Q3") (pin "3") (pinfunction "S_3") (pintype "unspecified"))
      (node (ref "Q4") (pin "3") (pinfunction "S_3") (pintype "unspecified"))
      (node (ref "Q5") (pin "3") (pinfunction "S_3") (pintype "unspecified"))
      (node (ref "Q6") (pin "3") (pinfunction "S_3") (pintype "unspecified"))
      (node (ref "Q7") (pin "3") (pinfunction "S_3") (pintype "unspecified"))
      (node (ref "Q8") (pin "3") (pinfunction "S_3") (pintype "unspecified"))
      (node (ref "Q9") (pin "3") (pinfunction "S_3") (pintype "unspecified"))
      (node (ref "R1") (pin "2") (pinfunction "2_2") (pintype "input"))
      (node (ref "R18") (pin "2") (pinfunction "2_2") (pintype "input"))
      (node (ref "R2") (pin "2") (pinfunction "2_2") (pintype "input"))
      (node (ref "R24") (pin "1") (pinfunction "1_1") (pintype "unspecified"))
      (node (ref "R25") (pin "1") (pinfunction "1_1") (pintype "input"))
      (node (ref "R3") (pin "2") (pinfunction "2_2") (pintype "input"))
      (node (ref "R37") (pin "2") (pinfunction "2_2") (pintype "input"))
      (node (ref "R4") (pin "2") (pinfunction "2_2") (pintype "input"))
      (node (ref "R5") (pin "2") (pinfunction "2_2") (pintype "input"))
      (node (ref "R51") (pin "1") (pinfunction "1_1") (pintype "input"))
      (node (ref "R54") (pin "2") (pinfunction "2_2") (pintype "input"))
      (node (ref "R6") (pin "2") (pinfunction "2_2") (pintype "input"))
      (node (ref "R7") (pin "2") (pinfunction "2_2") (pintype "input"))
      (node (ref "R8") (pin "2") (pinfunction "2_2") (pintype "input"))
      (node (ref "U10") (pin "1") (pinfunction "1_1") (pintype "input"))
      (node (ref "U12") (pin "1") (pinfunction "1_1") (pintype "input"))
      (node (ref "U13") (pin "1") (pinfunction "GND_1") (pintype "unspecified"))
      (node (ref "U5") (pin "1") (pinfunction "ADDR_1") (pintype "input"))
      (node (ref "U7") (pin "14") (pinfunction "14_14") (pintype "unspecified"))
      (node (ref "U8") (pin "14") (pinfunction "14_14") (pintype "unspecified"))
      (node (ref "ZD1") (pin "2") (pinfunction "A_2") (pintype "unspecified"))
    )
    (net (code "36") (name "KEEP_ALIVE") (class "Default")
      (node (ref "D16") (pin "2") (pinfunction "A_2") (pintype "unspecified"))
      (node (ref "U7") (pin "12") (pinfunction "12_12") (pintype "unspecified"))
    )
    (net (code "37") (name "Net-(D15-C)") (class "Default")
      (node (ref "D15") (pin "1") (pinfunction "C_1") (pintype "unspecified"))
      (node (ref "D16") (pin "1") (pinfunction "C_1") (pintype "unspecified"))
      (node (ref "R38") (pin "2") (pinfunction "2_2") (pintype "unspecified"))
    )
    (net (code "38") (name "Net-(Q1-G)") (class "Default")
      (node (ref "Q1") (pin "1") (pinfunction "G_1") (pintype "unspecified"))
      (node (ref "R1") (pin "1") (pinfunction "1_1") (pintype "input"))
      (node (ref "R9") (pin "1") (pinfunction "1_1") (pintype "unspecified"))
    )
    (net (code "39") (name "Net-(Q2-G)") (class "Default")
      (node (ref "Q2") (pin "1") (pinfunction "G_1") (pintype "unspecified"))
      (node (ref "R10") (pin "1") (pinfunction "1_1") (pintype "unspecified"))
      (node (ref "R2") (pin "1") (pinfunction "1_1") (pintype "input"))
    )
    (net (code "40") (name "Net-(Q3-G)") (class "Default")
      (node (ref "Q3") (pin "1") (pinfunction "G_1") (pintype "unspecified"))
      (node (ref "R11") (pin "1") (pinfunction "1_1") (pintype "unspecified"))
      (node (ref "R3") (pin "1") (pinfunction "1_1") (pintype "input"))
    )
    (net (code "41") (name "Net-(Q4-G)") (class "Default")
      (node (ref "Q4") (pin "1") (pinfunction "G_1") (pintype "unspecified"))
      (node (ref "R12") (pin "1") (pinfunction "1_1") (pintype "unspecified"))
      (node (ref "R4") (pin "1") (pinfunction "1_1") (pintype "input"))
    )
    (net (code "42") (name "Net-(Q5-G)") (class "Default")
      (node (ref "Q5") (pin "1") (pinfunction "G_1") (pintype "unspecified"))
      (node (ref "R13") (pin "1") (pinfunction "1_1") (pintype "unspecified"))
      (node (ref "R5") (pin "1") (pinfunction "1_1") (pintype "input"))
    )
    (net (code "43") (name "Net-(Q6-G)") (class "Default")
      (node (ref "Q6") (pin "1") (pinfunction "G_1") (pintype "unspecified"))
      (node (ref "R14") (pin "1") (pinfunction "1_1") (pintype "unspecified"))
      (node (ref "R6") (pin "1") (pinfunction "1_1") (pintype "input"))
    )
    (net (code "44") (name "Net-(Q7-G)") (class "Default")
      (node (ref "Q7") (pin "1") (pinfunction "G_1") (pintype "unspecified"))
      (node (ref "R15") (pin "1") (pinfunction "1_1") (pintype "unspecified"))
      (node (ref "R7") (pin "1") (pinfunction "1_1") (pintype "input"))
    )
    (net (code "45") (name "Net-(Q8-G)") (class "Default")
      (node (ref "Q8") (pin "1") (pinfunction "G_1") (pintype "unspecified"))
      (node (ref "R16") (pin "1") (pinfunction "1_1") (pintype "unspecified"))
      (node (ref "R8") (pin "1") (pinfunction "1_1") (pintype "input"))
    )
    (net (code "46") (name "Net-(Q9-G)") (class "Default")
      (node (ref "Q9") (pin "1") (pinfunction "G_1") (pintype "unspecified"))
      (node (ref "R17") (pin "1") (pinfunction "1_1") (pintype "unspecified"))
      (node (ref "R18") (pin "1") (pinfunction "1_1") (pintype "input"))
    )
    (net (code "47") (name "Net-(Q14-D)") (class "Default")
      (node (ref "Q14") (pin "2") (pinfunction "D_2") (pintype "unspecified"))
      (node (ref "R40") (pin "1") (pinfunction "1_1") (pintype "input"))
    )
    (net (code "48") (name "Net-(Q14-G)") (class "Default")
      (node (ref "Q14") (pin "1") (pinfunction "G_1") (pintype "unspecified"))
      (node (ref "R37") (pin "1") (pinfunction "1_1") (pintype "input"))
      (node (ref "R38") (pin "1") (pinfunction "1_1") (pintype "unspecified"))
    )
    (net (code "49") (name "Net-(Q15-G)") (class "Default")
      (node (ref "Q15") (pin "1") (pinfunction "G_1") (pintype "unspecified"))
      (node (ref "R39") (pin "2") (pinfunction "2_2") (pintype "input"))
      (node (ref "R40") (pin "2") (pinfunction "2_2") (pintype "input"))
    )
    (net (code "50") (name "Net-(Q16-G)") (class "Default")
      (node (ref "Q16") (pin "1") (pinfunction "G_1") (pintype "unspecified"))
      (node (ref "R54") (pin "1") (pinfunction "1_1") (pintype "input"))
      (node (ref "R55") (pin "1") (pinfunction "1_1") (pintype "unspecified"))
    )
    (net (code "51") (name "Net-(U4-ALERT{slash}RDY)") (class "Default")
      (node (ref "R41") (pin "2") (pinfunction "2_2") (pintype "input"))
      (node (ref "U4") (pin "2") (pinfunction "ALERT/RDY_2") (pintype "output"))
    )
    (net (code "52") (name "Net-(U4-GND)") (class "Default")
      (node (ref "C1") (pin "2") (pinfunction "2_2") (pintype "unspecified"))
      (node (ref "U10") (pin "2") (pinfunction "2_2") (pintype "input"))
      (node (ref "U4") (pin "3") (pinfunction "GND_3") (pintype "unspecified"))
    )
    (net (code "53") (name "Net-(U4-VDD)") (class "Default")
      (node (ref "C1") (pin "1") (pinfunction "1_1") (pintype "unspecified"))
      (node (ref "R33") (pin "1") (pinfunction "1_1") (pintype "input"))
      (node (ref "R41") (pin "1") (pinfunction "1_1") (pintype "input"))
      (node (ref "R42") (pin "1") (pinfunction "1_1") (pintype "input"))
      (node (ref "U4") (pin "8") (pinfunction "VDD_8") (pintype "unspecified"))
      (node (ref "U9") (pin "2") (pinfunction "2_2") (pintype "input"))
    )
    (net (code "54") (name "Net-(U5-ALERT{slash}RDY)") (class "Default")
      (node (ref "R43") (pin "2") (pinfunction "2_2") (pintype "input"))
      (node (ref "U5") (pin "2") (pinfunction "ALERT/RDY_2") (pintype "output"))
    )
    (net (code "55") (name "Net-(U5-GND)") (class "Default")
      (node (ref "C2") (pin "2") (pinfunction "2_2") (pintype "unspecified"))
      (node (ref "U12") (pin "2") (pinfunction "2_2") (pintype "input"))
      (node (ref "U5") (pin "3") (pinfunction "GND_3") (pintype "unspecified"))
    )
    (net (code "56") (name "Net-(U5-VDD)") (class "Default")
      (node (ref "C2") (pin "1") (pinfunction "1_1") (pintype "unspecified"))
      (node (ref "R43") (pin "1") (pinfunction "1_1") (pintype "input"))
      (node (ref "R44") (pin "2") (pinfunction "2_2") (pintype "input"))
      (node (ref "R45") (pin "2") (pinfunction "2_2") (pintype "input"))
      (node (ref "U11") (pin "2") (pinfunction "2_2") (pintype "input"))
      (node (ref "U5") (pin "8") (pinfunction "VDD_8") (pintype "unspecified"))
    )
    (net (code "57") (name "Net-(U13-SW)") (class "Default")
      (node (ref "C12") (pin "2") (pinfunction "2_2") (pintype "input"))
      (node (ref "L3") (pin "1") (pinfunction "1_1") (pintype "unspecified"))
      (node (ref "U13") (pin "2") (pinfunction "SW_2") (pintype "unspecified"))
    )
    (net (code "58") (name "Net-(U13-VBST)") (class "Default")
      (node (ref "C12") (pin "1") (pinfunction "1_1") (pintype "input"))
      (node (ref "U13") (pin "6") (pinfunction "VBST_6") (pintype "unspecified"))
    )
    (net (code "59") (name "Net-(U13-VFB)") (class "Default")
      (node (ref "R50") (pin "1") (pinfunction "1_1") (pintype "input"))
      (node (ref "R51") (pin "2") (pinfunction "2_2") (pintype "input"))
      (node (ref "U13") (pin "4") (pinfunction "VFB_4") (pintype "unspecified"))
    )
    (net (code "60") (name "RDI_TRIGGER") (class "Default")
      (node (ref "R14") (pin "2") (pinfunction "2_2") (pintype "unspecified"))
      (node (ref "U7") (pin "10") (pinfunction "10_10") (pintype "unspecified"))
    )
    (net (code "61") (name "RDO_TRIGGER") (class "Default")
      (node (ref "R13") (pin "2") (pinfunction "2_2") (pintype "unspecified"))
      (node (ref "U7") (pin "9") (pinfunction "9_9") (pintype "unspecified"))
    )
    (net (code "62") (name "RPI_TRIGGER") (class "Default")
      (node (ref "R16") (pin "2") (pinfunction "2_2") (pintype "unspecified"))
      (node (ref "U8") (pin "6") (pinfunction "6_6") (pintype "unspecified"))
    )
    (net (code "63") (name "RPO_TRIGGER") (class "Default")
      (node (ref "R15") (pin "2") (pinfunction "2_2") (pintype "unspecified"))
      (node (ref "U7") (pin "7") (pinfunction "7_7") (pintype "unspecified"))
    )
    (net (code "64") (name "RX") (class "Default")
      (node (ref "CN5") (pin "8") (pinfunction "8_8") (pintype "unspecified"))
      (node (ref "U8") (pin "12") (pinfunction "12_12") (pintype "unspecified"))
    )
    (net (code "65") (name "SCL") (class "Default")
      (node (ref "CN5") (pin "5") (pinfunction "5_5") (pintype "unspecified"))
      (node (ref "Q13") (pin "2") (pinfunction "S_2") (pintype "unspecified"))
      (node (ref "R28") (pin "1") (pinfunction "1_1") (pintype "input"))
      (node (ref "U8") (pin "2") (pinfunction "2_2") (pintype "unspecified"))
    )
    (net (code "66") (name "SDA") (class "Default")
      (node (ref "CN5") (pin "7") (pinfunction "7_7") (pintype "unspecified"))
      (node (ref "Q12") (pin "2") (pinfunction "S_2") (pintype "unspecified"))
      (node (ref "R30") (pin "1") (pinfunction "1_1") (pintype "input"))
      (node (ref "U8") (pin "5") (pinfunction "5_5") (pintype "unspecified"))
    )
    (net (code "67") (name "TANKPRESSURESIG") (class "Default")
      (node (ref "R19") (pin "1") (pinfunction "1_1") (pintype "unspecified"))
      (node (ref "R24") (pin "2") (pinfunction "2_2") (pintype "unspecified"))
      (node (ref "U7") (pin "6") (pinfunction "6_6") (pintype "unspecified"))
    )
    (net (code "68") (name "TX") (class "Default")
      (node (ref "CN5") (pin "6") (pinfunction "6_6") (pintype "unspecified"))
      (node (ref "U8") (pin "11") (pinfunction "11_11") (pintype "unspecified"))
    )
    (net (code "69") (name "VCC") (class "Default")
      (node (ref "C17") (pin "1") (pinfunction "1_1") (pintype "input"))
      (node (ref "CN7") (pin "1") (pinfunction "1_1") (pintype "unspecified"))
      (node (ref "D1") (pin "1") (pinfunction "C_1") (pintype "unspecified"))
      (node (ref "D10") (pin "1") (pinfunction "C_1") (pintype "unspecified"))
      (node (ref "D17") (pin "1") (pinfunction "C_1") (pintype "unspecified"))
      (node (ref "D2") (pin "1") (pinfunction "C_1") (pintype "unspecified"))
      (node (ref "D3") (pin "1") (pinfunction "C_1") (pintype "unspecified"))
      (node (ref "D4") (pin "1") (pinfunction "C_1") (pintype "unspecified"))
      (node (ref "D5") (pin "1") (pinfunction "C_1") (pintype "unspecified"))
      (node (ref "D6") (pin "1") (pinfunction "C_1") (pintype "unspecified"))
      (node (ref "D7") (pin "1") (pinfunction "C_1") (pintype "unspecified"))
      (node (ref "D8") (pin "1") (pinfunction "C_1") (pintype "unspecified"))
      (node (ref "D9") (pin "1") (pinfunction "C_1") (pintype "unspecified"))
      (node (ref "Q15") (pin "3") (pinfunction "S_3") (pintype "unspecified"))
      (node (ref "R39") (pin "1") (pinfunction "1_1") (pintype "input"))
    )
    (net (code "70") (name "unconnected-(CN2-Pad7)") (class "Default")
      (node (ref "CN2") (pin "7") (pinfunction "7_7") (pintype "unspecified+no_connect"))
    )
    (net (code "71") (name "unconnected-(CN2-Pad9)") (class "Default")
      (node (ref "CN2") (pin "9") (pinfunction "9_9") (pintype "unspecified+no_connect"))
    )
    (net (code "72") (name "unconnected-(CN2-Pad11)") (class "Default")
      (node (ref "CN2") (pin "11") (pinfunction "11_11") (pintype "unspecified+no_connect"))
    )
    (net (code "73") (name "unconnected-(CN3-Pad11)") (class "Default")
      (node (ref "CN3") (pin "11") (pinfunction "11_11") (pintype "unspecified+no_connect"))
    )
    (net (code "74") (name "unconnected-(U7-Pad1)") (class "Default")
      (node (ref "U7") (pin "1") (pinfunction "1_1") (pintype "unspecified+no_connect"))
    )
    (net (code "75") (name "unconnected-(U7-Pad2)") (class "Default")
      (node (ref "U7") (pin "2") (pinfunction "2_2") (pintype "unspecified+no_connect"))
    )
    (net (code "76") (name "unconnected-(U7-Pad3)") (class "Default")
      (node (ref "U7") (pin "3") (pinfunction "3_3") (pintype "unspecified+no_connect"))
    )
    (net (code "77") (name "unconnected-(U8-Pad3)") (class "Default")
      (node (ref "U8") (pin "3") (pinfunction "3_3") (pintype "unspecified+no_connect"))
    )
    (net (code "78") (name "unconnected-(U8-Pad4)") (class "Default")
      (node (ref "U8") (pin "4") (pinfunction "4_4") (pintype "unspecified+no_connect"))
    )
    (net (code "79") (name "unconnected-(U8-Pad8)") (class "Default")
      (node (ref "U8") (pin "8") (pinfunction "8_8") (pintype "unspecified+no_connect"))
    )
    (net (code "80") (name "unconnected-(U8-Pad10)") (class "Default")
      (node (ref "U8") (pin "10") (pinfunction "10_10") (pintype "unspecified+no_connect"))
    )
    (net (code "81") (name "unconnected-(U8-Pad13)") (class "Default")
      (node (ref "U8") (pin "13") (pinfunction "13_13") (pintype "unspecified+no_connect"))
    )
  )
)
